# RGB.net
KiCad netlist of a schematic drawn in Altium Designer
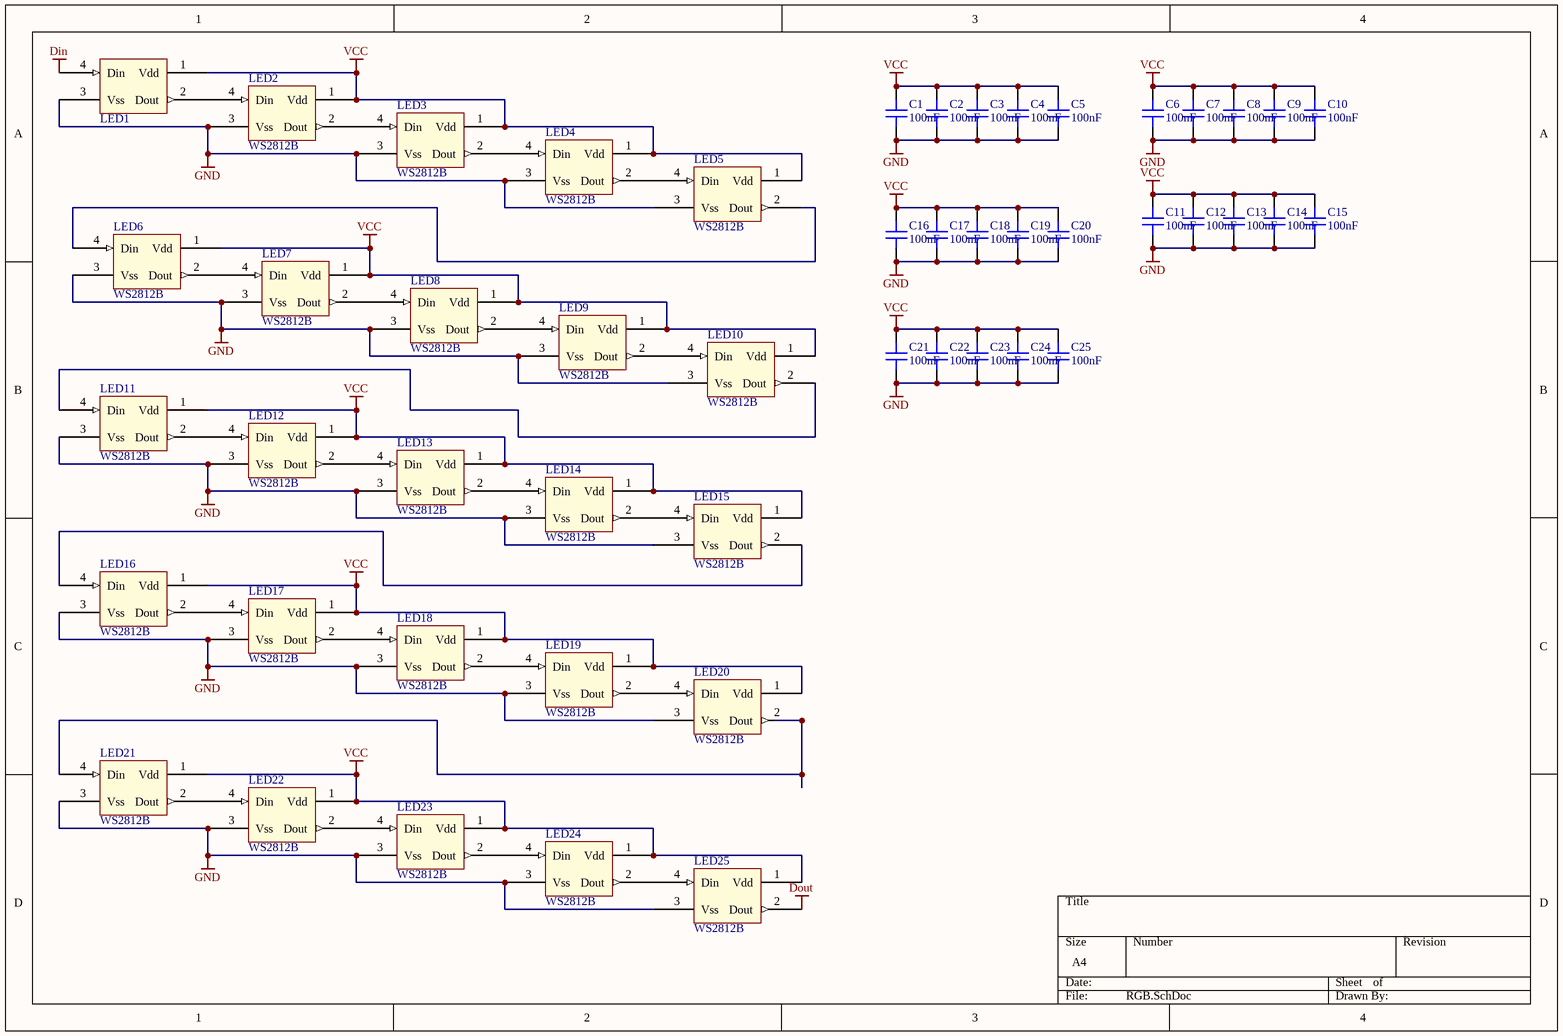
[diagram p0: RGB.SchDoc]

(export (version "E")
  (design (tool "Eeschema 10.0.6"))
  (components
    (comp (ref "C1")
      (value "100nF")
      (footprint "CAP 1206/3216")
      (description "SMT Capacitor")
      (libsource (lib "Cap_Res") (part "Capacitor"))
    )
    (comp (ref "C2")
      (value "100nF")
      (footprint "CAP 1206/3216")
      (description "SMT Capacitor")
      (libsource (lib "Cap_Res") (part "Capacitor"))
    )
    (comp (ref "C3")
      (value "100nF")
      (footprint "CAP 1206/3216")
      (description "SMT Capacitor")
      (libsource (lib "Cap_Res") (part "Capacitor"))
    )
    (comp (ref "C4")
      (value "100nF")
      (footprint "CAP 1206/3216")
      (description "SMT Capacitor")
      (libsource (lib "Cap_Res") (part "Capacitor"))
    )
    (comp (ref "C5")
      (value "100nF")
      (footprint "CAP 1206/3216")
      (description "SMT Capacitor")
      (libsource (lib "Cap_Res") (part "Capacitor"))
    )
    (comp (ref "C6")
      (value "100nF")
      (footprint "CAP 1206/3216")
      (description "SMT Capacitor")
      (libsource (lib "Cap_Res") (part "Capacitor"))
    )
    (comp (ref "C7")
      (value "100nF")
      (footprint "CAP 1206/3216")
      (description "SMT Capacitor")
      (libsource (lib "Cap_Res") (part "Capacitor"))
    )
    (comp (ref "C8")
      (value "100nF")
      (footprint "CAP 1206/3216")
      (description "SMT Capacitor")
      (libsource (lib "Cap_Res") (part "Capacitor"))
    )
    (comp (ref "C9")
      (value "100nF")
      (footprint "CAP 1206/3216")
      (description "SMT Capacitor")
      (libsource (lib "Cap_Res") (part "Capacitor"))
    )
    (comp (ref "C10")
      (value "100nF")
      (footprint "CAP 1206/3216")
      (description "SMT Capacitor")
      (libsource (lib "Cap_Res") (part "Capacitor"))
    )
    (comp (ref "C11")
      (value "100nF")
      (footprint "CAP 1206/3216")
      (description "SMT Capacitor")
      (libsource (lib "Cap_Res") (part "Capacitor"))
    )
    (comp (ref "C12")
      (value "100nF")
      (footprint "CAP 1206/3216")
      (description "SMT Capacitor")
      (libsource (lib "Cap_Res") (part "Capacitor"))
    )
    (comp (ref "C13")
      (value "100nF")
      (footprint "CAP 1206/3216")
      (description "SMT Capacitor")
      (libsource (lib "Cap_Res") (part "Capacitor"))
    )
    (comp (ref "C14")
      (value "100nF")
      (footprint "CAP 1206/3216")
      (description "SMT Capacitor")
      (libsource (lib "Cap_Res") (part "Capacitor"))
    )
    (comp (ref "C15")
      (value "100nF")
      (footprint "CAP 1206/3216")
      (description "SMT Capacitor")
      (libsource (lib "Cap_Res") (part "Capacitor"))
    )
    (comp (ref "C16")
      (value "100nF")
      (footprint "CAP 1206/3216")
      (description "SMT Capacitor")
      (libsource (lib "Cap_Res") (part "Capacitor"))
    )
    (comp (ref "C17")
      (value "100nF")
      (footprint "CAP 1206/3216")
      (description "SMT Capacitor")
      (libsource (lib "Cap_Res") (part "Capacitor"))
    )
    (comp (ref "C18")
      (value "100nF")
      (footprint "CAP 1206/3216")
      (description "SMT Capacitor")
      (libsource (lib "Cap_Res") (part "Capacitor"))
    )
    (comp (ref "C19")
      (value "100nF")
      (footprint "CAP 1206/3216")
      (description "SMT Capacitor")
      (libsource (lib "Cap_Res") (part "Capacitor"))
    )
    (comp (ref "C20")
      (value "100nF")
      (footprint "CAP 1206/3216")
      (description "SMT Capacitor")
      (libsource (lib "Cap_Res") (part "Capacitor"))
    )
    (comp (ref "C21")
      (value "100nF")
      (footprint "CAP 1206/3216")
      (description "SMT Capacitor")
      (libsource (lib "Cap_Res") (part "Capacitor"))
    )
    (comp (ref "C22")
      (value "100nF")
      (footprint "CAP 1206/3216")
      (description "SMT Capacitor")
      (libsource (lib "Cap_Res") (part "Capacitor"))
    )
    (comp (ref "C23")
      (value "100nF")
      (footprint "CAP 1206/3216")
      (description "SMT Capacitor")
      (libsource (lib "Cap_Res") (part "Capacitor"))
    )
    (comp (ref "C24")
      (value "100nF")
      (footprint "CAP 1206/3216")
      (description "SMT Capacitor")
      (libsource (lib "Cap_Res") (part "Capacitor"))
    )
    (comp (ref "C25")
      (value "100nF")
      (footprint "CAP 1206/3216")
      (description "SMT Capacitor")
      (libsource (lib "Cap_Res") (part "Capacitor"))
    )
    (comp (ref "LED1") (value "WS2812B") (footprint "WS2812B") (libsource (lib "Other") (part "WS2812B")))
    (comp (ref "LED2") (value "WS2812B") (footprint "WS2812B") (libsource (lib "WS2812") (part "WS2812B")))
    (comp (ref "LED3") (value "WS2812B") (footprint "WS2812B") (libsource (lib "WS2812") (part "WS2812B")))
    (comp (ref "LED4") (value "WS2812B") (footprint "WS2812B") (libsource (lib "WS2812") (part "WS2812B")))
    (comp (ref "LED5") (value "WS2812B") (footprint "WS2812B") (libsource (lib "Other") (part "WS2812B")))
    (comp (ref "LED6") (value "WS2812B") (footprint "WS2812B") (libsource (lib "Other") (part "WS2812B")))
    (comp (ref "LED7") (value "WS2812B") (footprint "WS2812B") (libsource (lib "WS2812") (part "WS2812B")))
    (comp (ref "LED8") (value "WS2812B") (footprint "WS2812B") (libsource (lib "WS2812") (part "WS2812B")))
    (comp (ref "LED9") (value "WS2812B") (footprint "WS2812B") (libsource (lib "WS2812") (part "WS2812B")))
    (comp (ref "LED10") (value "WS2812B") (footprint "WS2812B") (libsource (lib "WS2812") (part "WS2812B")))
    (comp (ref "LED11") (value "WS2812B") (footprint "WS2812B") (libsource (lib "WS2812") (part "WS2812B")))
    (comp (ref "LED12") (value "WS2812B") (footprint "WS2812B") (libsource (lib "WS2812") (part "WS2812B")))
    (comp (ref "LED13") (value "WS2812B") (footprint "WS2812B") (libsource (lib "WS2812") (part "WS2812B")))
    (comp (ref "LED14") (value "WS2812B") (footprint "WS2812B") (libsource (lib "WS2812") (part "WS2812B")))
    (comp (ref "LED15") (value "WS2812B") (footprint "WS2812B") (libsource (lib "WS2812") (part "WS2812B")))
    (comp (ref "LED16") (value "WS2812B") (footprint "WS2812B") (libsource (lib "WS2812") (part "WS2812B")))
    (comp (ref "LED17") (value "WS2812B") (footprint "WS2812B") (libsource (lib "WS2812") (part "WS2812B")))
    (comp (ref "LED18") (value "WS2812B") (footprint "WS2812B") (libsource (lib "WS2812") (part "WS2812B")))
    (comp (ref "LED19") (value "WS2812B") (footprint "WS2812B") (libsource (lib "WS2812") (part "WS2812B")))
    (comp (ref "LED20") (value "WS2812B") (footprint "WS2812B") (libsource (lib "WS2812") (part "WS2812B")))
    (comp (ref "LED21") (value "WS2812B") (footprint "WS2812B") (libsource (lib "WS2812") (part "WS2812B")))
    (comp (ref "LED22") (value "WS2812B") (footprint "WS2812B") (libsource (lib "WS2812") (part "WS2812B")))
    (comp (ref "LED23") (value "WS2812B") (footprint "WS2812B") (libsource (lib "WS2812") (part "WS2812B")))
    (comp (ref "LED24") (value "WS2812B") (footprint "WS2812B") (libsource (lib "WS2812") (part "WS2812B")))
    (comp (ref "LED25") (value "WS2812B") (footprint "WS2812B") (libsource (lib "WS2812") (part "WS2812B")))
  )
  (nets
    (net (code "1") (name "Din") (class "Default")
      (node (ref "LED1") (pin "4") (pinfunction "Din_4") (pintype "input"))
    )
    (net (code "2") (name "Dout") (class "Default")
      (node (ref "LED25") (pin "2") (pinfunction "Dout_2") (pintype "output"))
    )
    (net (code "3") (name "GND") (class "Default")
      (node (ref "C1") (pin "1") (pinfunction "1_1") (pintype "passive"))
      (node (ref "C10") (pin "1") (pinfunction "1_1") (pintype "passive"))
      (node (ref "C11") (pin "1") (pinfunction "1_1") (pintype "passive"))
      (node (ref "C12") (pin "1") (pinfunction "1_1") (pintype "passive"))
      (node (ref "C13") (pin "1") (pinfunction "1_1") (pintype "passive"))
      (node (ref "C14") (pin "1") (pinfunction "1_1") (pintype "passive"))
      (node (ref "C15") (pin "1") (pinfunction "1_1") (pintype "passive"))
      (node (ref "C16") (pin "1") (pinfunction "1_1") (pintype "passive"))
      (node (ref "C17") (pin "1") (pinfunction "1_1") (pintype "passive"))
      (node (ref "C18") (pin "1") (pinfunction "1_1") (pintype "passive"))
      (node (ref "C19") (pin "1") (pinfunction "1_1") (pintype "passive"))
      (node (ref "C2") (pin "1") (pinfunction "1_1") (pintype "passive"))
      (node (ref "C20") (pin "1") (pinfunction "1_1") (pintype "passive"))
      (node (ref "C21") (pin "1") (pinfunction "1_1") (pintype "passive"))
      (node (ref "C22") (pin "1") (pinfunction "1_1") (pintype "passive"))
      (node (ref "C23") (pin "1") (pinfunction "1_1") (pintype "passive"))
      (node (ref "C24") (pin "1") (pinfunction "1_1") (pintype "passive"))
      (node (ref "C25") (pin "1") (pinfunction "1_1") (pintype "passive"))
      (node (ref "C3") (pin "1") (pinfunction "1_1") (pintype "passive"))
      (node (ref "C4") (pin "1") (pinfunction "1_1") (pintype "passive"))
      (node (ref "C5") (pin "1") (pinfunction "1_1") (pintype "passive"))
      (node (ref "C6") (pin "1") (pinfunction "1_1") (pintype "passive"))
      (node (ref "C7") (pin "1") (pinfunction "1_1") (pintype "passive"))
      (node (ref "C8") (pin "1") (pinfunction "1_1") (pintype "passive"))
      (node (ref "C9") (pin "1") (pinfunction "1_1") (pintype "passive"))
      (node (ref "LED1") (pin "3") (pinfunction "Vss_3") (pintype "power_in"))
      (node (ref "LED10") (pin "3") (pinfunction "Vss_3") (pintype "power_in"))
      (node (ref "LED11") (pin "3") (pinfunction "Vss_3") (pintype "power_in"))
      (node (ref "LED12") (pin "3") (pinfunction "Vss_3") (pintype "power_in"))
      (node (ref "LED13") (pin "3") (pinfunction "Vss_3") (pintype "power_in"))
      (node (ref "LED14") (pin "3") (pinfunction "Vss_3") (pintype "power_in"))
      (node (ref "LED15") (pin "3") (pinfunction "Vss_3") (pintype "power_in"))
      (node (ref "LED16") (pin "3") (pinfunction "Vss_3") (pintype "power_in"))
      (node (ref "LED17") (pin "3") (pinfunction "Vss_3") (pintype "power_in"))
      (node (ref "LED18") (pin "3") (pinfunction "Vss_3") (pintype "power_in"))
      (node (ref "LED19") (pin "3") (pinfunction "Vss_3") (pintype "power_in"))
      (node (ref "LED2") (pin "3") (pinfunction "Vss_3") (pintype "power_in"))
      (node (ref "LED20") (pin "3") (pinfunction "Vss_3") (pintype "power_in"))
      (node (ref "LED21") (pin "3") (pinfunction "Vss_3") (pintype "power_in"))
      (node (ref "LED22") (pin "3") (pinfunction "Vss_3") (pintype "power_in"))
      (node (ref "LED23") (pin "3") (pinfunction "Vss_3") (pintype "power_in"))
      (node (ref "LED24") (pin "3") (pinfunction "Vss_3") (pintype "power_in"))
      (node (ref "LED25") (pin "3") (pinfunction "Vss_3") (pintype "power_in"))
      (node (ref "LED3") (pin "3") (pinfunction "Vss_3") (pintype "power_in"))
      (node (ref "LED4") (pin "3") (pinfunction "Vss_3") (pintype "power_in"))
      (node (ref "LED5") (pin "3") (pinfunction "Vss_3") (pintype "power_in"))
      (node (ref "LED6") (pin "3") (pinfunction "Vss_3") (pintype "power_in"))
      (node (ref "LED7") (pin "3") (pinfunction "Vss_3") (pintype "power_in"))
      (node (ref "LED8") (pin "3") (pinfunction "Vss_3") (pintype "power_in"))
      (node (ref "LED9") (pin "3") (pinfunction "Vss_3") (pintype "power_in"))
    )
    (net (code "4") (name "Net-(LED1-Dout)") (class "Default")
      (node (ref "LED1") (pin "2") (pinfunction "Dout_2") (pintype "output"))
      (node (ref "LED2") (pin "4") (pinfunction "Din_4") (pintype "input"))
    )
    (net (code "5") (name "Net-(LED2-Dout)") (class "Default")
      (node (ref "LED2") (pin "2") (pinfunction "Dout_2") (pintype "output"))
      (node (ref "LED3") (pin "4") (pinfunction "Din_4") (pintype "input"))
    )
    (net (code "6") (name "Net-(LED3-Dout)") (class "Default")
      (node (ref "LED3") (pin "2") (pinfunction "Dout_2") (pintype "output"))
      (node (ref "LED4") (pin "4") (pinfunction "Din_4") (pintype "input"))
    )
    (net (code "7") (name "Net-(LED4-Dout)") (class "Default")
      (node (ref "LED4") (pin "2") (pinfunction "Dout_2") (pintype "output"))
      (node (ref "LED5") (pin "4") (pinfunction "Din_4") (pintype "input"))
    )
    (net (code "8") (name "Net-(LED5-Dout)") (class "Default")
      (node (ref "LED5") (pin "2") (pinfunction "Dout_2") (pintype "output"))
      (node (ref "LED6") (pin "4") (pinfunction "Din_4") (pintype "input"))
    )
    (net (code "9") (name "Net-(LED6-Dout)") (class "Default")
      (node (ref "LED6") (pin "2") (pinfunction "Dout_2") (pintype "output"))
      (node (ref "LED7") (pin "4") (pinfunction "Din_4") (pintype "input"))
    )
    (net (code "10") (name "Net-(LED7-Dout)") (class "Default")
      (node (ref "LED7") (pin "2") (pinfunction "Dout_2") (pintype "output"))
      (node (ref "LED8") (pin "4") (pinfunction "Din_4") (pintype "input"))
    )
    (net (code "11") (name "Net-(LED8-Dout)") (class "Default")
      (node (ref "LED8") (pin "2") (pinfunction "Dout_2") (pintype "output"))
      (node (ref "LED9") (pin "4") (pinfunction "Din_4") (pintype "input"))
    )
    (net (code "12") (name "Net-(LED10-Din)") (class "Default")
      (node (ref "LED10") (pin "4") (pinfunction "Din_4") (pintype "input"))
      (node (ref "LED9") (pin "2") (pinfunction "Dout_2") (pintype "output"))
    )
    (net (code "13") (name "Net-(LED10-Dout)") (class "Default")
      (node (ref "LED10") (pin "2") (pinfunction "Dout_2") (pintype "output"))
      (node (ref "LED11") (pin "4") (pinfunction "Din_4") (pintype "input"))
    )
    (net (code "14") (name "Net-(LED11-Dout)") (class "Default")
      (node (ref "LED11") (pin "2") (pinfunction "Dout_2") (pintype "output"))
      (node (ref "LED12") (pin "4") (pinfunction "Din_4") (pintype "input"))
    )
    (net (code "15") (name "Net-(LED12-Dout)") (class "Default")
      (node (ref "LED12") (pin "2") (pinfunction "Dout_2") (pintype "output"))
      (node (ref "LED13") (pin "4") (pinfunction "Din_4") (pintype "input"))
    )
    (net (code "16") (name "Net-(LED13-Dout)") (class "Default")
      (node (ref "LED13") (pin "2") (pinfunction "Dout_2") (pintype "output"))
      (node (ref "LED14") (pin "4") (pinfunction "Din_4") (pintype "input"))
    )
    (net (code "17") (name "Net-(LED14-Dout)") (class "Default")
      (node (ref "LED14") (pin "2") (pinfunction "Dout_2") (pintype "output"))
      (node (ref "LED15") (pin "4") (pinfunction "Din_4") (pintype "input"))
    )
    (net (code "18") (name "Net-(LED15-Dout)") (class "Default")
      (node (ref "LED15") (pin "2") (pinfunction "Dout_2") (pintype "output"))
      (node (ref "LED16") (pin "4") (pinfunction "Din_4") (pintype "input"))
    )
    (net (code "19") (name "Net-(LED16-Dout)") (class "Default")
      (node (ref "LED16") (pin "2") (pinfunction "Dout_2") (pintype "output"))
      (node (ref "LED17") (pin "4") (pinfunction "Din_4") (pintype "input"))
    )
    (net (code "20") (name "Net-(LED17-Dout)") (class "Default")
      (node (ref "LED17") (pin "2") (pinfunction "Dout_2") (pintype "output"))
      (node (ref "LED18") (pin "4") (pinfunction "Din_4") (pintype "input"))
    )
    (net (code "21") (name "Net-(LED18-Dout)") (class "Default")
      (node (ref "LED18") (pin "2") (pinfunction "Dout_2") (pintype "output"))
      (node (ref "LED19") (pin "4") (pinfunction "Din_4") (pintype "input"))
    )
    (net (code "22") (name "Net-(LED19-Dout)") (class "Default")
      (node (ref "LED19") (pin "2") (pinfunction "Dout_2") (pintype "output"))
      (node (ref "LED20") (pin "4") (pinfunction "Din_4") (pintype "input"))
    )
    (net (code "23") (name "Net-(LED20-Dout)") (class "Default")
      (node (ref "LED20") (pin "2") (pinfunction "Dout_2") (pintype "output"))
      (node (ref "LED21") (pin "4") (pinfunction "Din_4") (pintype "input"))
    )
    (net (code "24") (name "Net-(LED21-Dout)") (class "Default")
      (node (ref "LED21") (pin "2") (pinfunction "Dout_2") (pintype "output"))
      (node (ref "LED22") (pin "4") (pinfunction "Din_4") (pintype "input"))
    )
    (net (code "25") (name "Net-(LED22-Dout)") (class "Default")
      (node (ref "LED22") (pin "2") (pinfunction "Dout_2") (pintype "output"))
      (node (ref "LED23") (pin "4") (pinfunction "Din_4") (pintype "input"))
    )
    (net (code "26") (name "Net-(LED23-Dout)") (class "Default")
      (node (ref "LED23") (pin "2") (pinfunction "Dout_2") (pintype "output"))
      (node (ref "LED24") (pin "4") (pinfunction "Din_4") (pintype "input"))
    )
    (net (code "27") (name "Net-(LED24-Dout)") (class "Default")
      (node (ref "LED24") (pin "2") (pinfunction "Dout_2") (pintype "output"))
      (node (ref "LED25") (pin "4") (pinfunction "Din_4") (pintype "input"))
    )
    (net (code "28") (name "VCC") (class "Default")
      (node (ref "C1") (pin "2") (pinfunction "2_2") (pintype "passive"))
      (node (ref "C10") (pin "2") (pinfunction "2_2") (pintype "passive"))
      (node (ref "C11") (pin "2") (pinfunction "2_2") (pintype "passive"))
      (node (ref "C12") (pin "2") (pinfunction "2_2") (pintype "passive"))
      (node (ref "C13") (pin "2") (pinfunction "2_2") (pintype "passive"))
      (node (ref "C14") (pin "2") (pinfunction "2_2") (pintype "passive"))
      (node (ref "C15") (pin "2") (pinfunction "2_2") (pintype "passive"))
      (node (ref "C16") (pin "2") (pinfunction "2_2") (pintype "passive"))
      (node (ref "C17") (pin "2") (pinfunction "2_2") (pintype "passive"))
      (node (ref "C18") (pin "2") (pinfunction "2_2") (pintype "passive"))
      (node (ref "C19") (pin "2") (pinfunction "2_2") (pintype "passive"))
      (node (ref "C2") (pin "2") (pinfunction "2_2") (pintype "passive"))
      (node (ref "C20") (pin "2") (pinfunction "2_2") (pintype "passive"))
      (node (ref "C21") (pin "2") (pinfunction "2_2") (pintype "passive"))
      (node (ref "C22") (pin "2") (pinfunction "2_2") (pintype "passive"))
      (node (ref "C23") (pin "2") (pinfunction "2_2") (pintype "passive"))
      (node (ref "C24") (pin "2") (pinfunction "2_2") (pintype "passive"))
      (node (ref "C25") (pin "2") (pinfunction "2_2") (pintype "passive"))
      (node (ref "C3") (pin "2") (pinfunction "2_2") (pintype "passive"))
      (node (ref "C4") (pin "2") (pinfunction "2_2") (pintype "passive"))
      (node (ref "C5") (pin "2") (pinfunction "2_2") (pintype "passive"))
      (node (ref "C6") (pin "2") (pinfunction "2_2") (pintype "passive"))
      (node (ref "C7") (pin "2") (pinfunction "2_2") (pintype "passive"))
      (node (ref "C8") (pin "2") (pinfunction "2_2") (pintype "passive"))
      (node (ref "C9") (pin "2") (pinfunction "2_2") (pintype "passive"))
      (node (ref "LED1") (pin "1") (pinfunction "Vdd_1") (pintype "power_in"))
      (node (ref "LED10") (pin "1") (pinfunction "Vdd_1") (pintype "power_in"))
      (node (ref "LED11") (pin "1") (pinfunction "Vdd_1") (pintype "power_in"))
      (node (ref "LED12") (pin "1") (pinfunction "Vdd_1") (pintype "power_in"))
      (node (ref "LED13") (pin "1") (pinfunction "Vdd_1") (pintype "power_in"))
      (node (ref "LED14") (pin "1") (pinfunction "Vdd_1") (pintype "power_in"))
      (node (ref "LED15") (pin "1") (pinfunction "Vdd_1") (pintype "power_in"))
      (node (ref "LED16") (pin "1") (pinfunction "Vdd_1") (pintype "power_in"))
      (node (ref "LED17") (pin "1") (pinfunction "Vdd_1") (pintype "power_in"))
      (node (ref "LED18") (pin "1") (pinfunction "Vdd_1") (pintype "power_in"))
      (node (ref "LED19") (pin "1") (pinfunction "Vdd_1") (pintype "power_in"))
      (node (ref "LED2") (pin "1") (pinfunction "Vdd_1") (pintype "power_in"))
      (node (ref "LED20") (pin "1") (pinfunction "Vdd_1") (pintype "power_in"))
      (node (ref "LED21") (pin "1") (pinfunction "Vdd_1") (pintype "power_in"))
      (node (ref "LED22") (pin "1") (pinfunction "Vdd_1") (pintype "power_in"))
      (node (ref "LED23") (pin "1") (pinfunction "Vdd_1") (pintype "power_in"))
      (node (ref "LED24") (pin "1") (pinfunction "Vdd_1") (pintype "power_in"))
      (node (ref "LED25") (pin "1") (pinfunction "Vdd_1") (pintype "power_in"))
      (node (ref "LED3") (pin "1") (pinfunction "Vdd_1") (pintype "power_in"))
      (node (ref "LED4") (pin "1") (pinfunction "Vdd_1") (pintype "power_in"))
      (node (ref "LED5") (pin "1") (pinfunction "Vdd_1") (pintype "power_in"))
      (node (ref "LED6") (pin "1") (pinfunction "Vdd_1") (pintype "power_in"))
      (node (ref "LED7") (pin "1") (pinfunction "Vdd_1") (pintype "power_in"))
      (node (ref "LED8") (pin "1") (pinfunction "Vdd_1") (pintype "power_in"))
      (node (ref "LED9") (pin "1") (pinfunction "Vdd_1") (pintype "power_in"))
    )
  )
)
